# i2c.net
KiCad netlist of a schematic drawn in Altium Designer
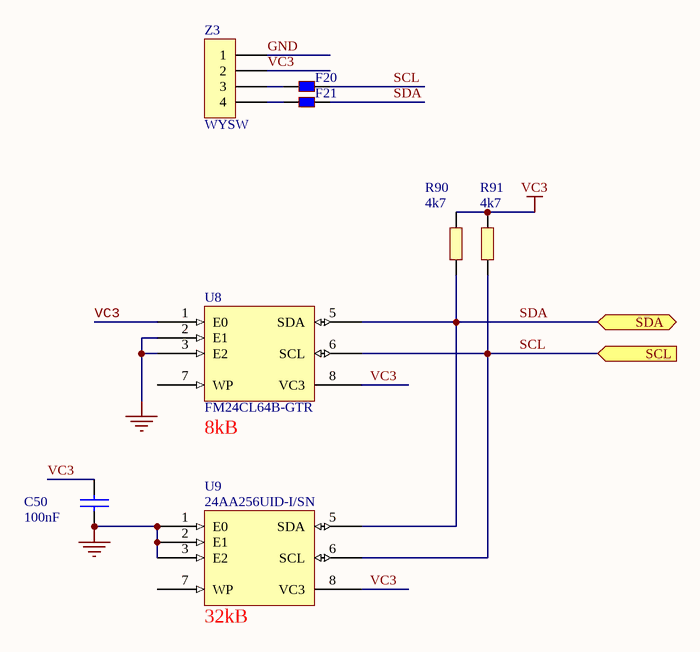
[diagram p0: i2c.SchDoc]

(export (version "E")
  (design (tool "Eeschema 10.0.6"))
  (components
    (comp (ref "C50")
      (value "100nF")
      (footprint "0603C")
      (description "Capacitor")
      (libsource (lib "*") (part "CAP"))
    )
    (comp (ref "F20")
      (value "BLM18BB141SN1D")
      (footprint "0603R")
      (description "Koralik ferrytowy")
      (libsource (lib "*") (part "1812"))
    )
    (comp (ref "F21")
      (value "BLM18BB141SN1D")
      (footprint "0603R")
      (description "Koralik ferrytowy")
      (libsource (lib "*") (part "1812"))
    )
    (comp (ref "R90") (value "4k7") (footprint "0603R") (libsource (lib "*") (part "RES3")))
    (comp (ref "R91") (value "4k7") (footprint "0603R") (libsource (lib "*") (part "RES3")))
    (comp (ref "U8") (value "FM24CL64B-GTR") (footprint "SO8") (libsource (lib "*") (part "AT24C02")))
    (comp (ref "U9") (value "24AA256UID-I/SN") (footprint "SO8") (libsource (lib "*") (part "AT24C02")))
    (comp (ref "Z3")
      (value "WYSW")
      (footprint "SSD1306_PR")
      (description "Connector")
      (libsource (lib "*") (part "CON4"))
    )
  )
  (nets
    (net (code "1") (name "/SCL") (class "Default")
      (node (ref "F20") (pin "2") (pintype "passive"))
      (node (ref "R91") (pin "2") (pintype "passive"))
      (node (ref "U8") (pin "6") (pinfunction "SCL_6") (pintype "bidirectional"))
      (node (ref "U9") (pin "6") (pinfunction "SCL_6") (pintype "bidirectional"))
    )
    (net (code "2") (name "/SDA") (class "Default")
      (node (ref "F21") (pin "2") (pintype "passive"))
      (node (ref "R90") (pin "2") (pintype "passive"))
      (node (ref "U8") (pin "5") (pinfunction "SDA_5") (pintype "bidirectional"))
      (node (ref "U9") (pin "5") (pinfunction "SDA_5") (pintype "bidirectional"))
    )
    (net (code "3") (name "GND") (class "Default")
      (node (ref "C50") (pin "2") (pinfunction "2_2") (pintype "passive"))
      (node (ref "U8") (pin "2") (pinfunction "E1_2") (pintype "input"))
      (node (ref "U8") (pin "3") (pinfunction "E2_3") (pintype "input"))
      (node (ref "U8") (pin "4") (pinfunction "GND_4") (pintype "power_in"))
      (node (ref "U9") (pin "1") (pinfunction "E0_1") (pintype "input"))
      (node (ref "U9") (pin "2") (pinfunction "E1_2") (pintype "input"))
      (node (ref "U9") (pin "3") (pinfunction "E2_3") (pintype "input"))
      (node (ref "U9") (pin "4") (pinfunction "GND_4") (pintype "power_in"))
      (node (ref "Z3") (pin "1") (pinfunction "1_1") (pintype "passive"))
    )
    (net (code "4") (name "Net-(F20-Pad1)") (class "Default")
      (node (ref "F20") (pin "1") (pintype "passive"))
      (node (ref "Z3") (pin "3") (pinfunction "3_3") (pintype "passive"))
    )
    (net (code "5") (name "Net-(F21-Pad1)") (class "Default")
      (node (ref "F21") (pin "1") (pintype "passive"))
      (node (ref "Z3") (pin "4") (pinfunction "4_4") (pintype "passive"))
    )
    (net (code "6") (name "VC3") (class "Default")
      (node (ref "C50") (pin "1") (pinfunction "1_1") (pintype "passive"))
      (node (ref "R90") (pin "1") (pintype "passive"))
      (node (ref "R91") (pin "1") (pintype "passive"))
      (node (ref "U8") (pin "1") (pinfunction "E0_1") (pintype "input"))
      (node (ref "U8") (pin "8") (pinfunction "VC3_8") (pintype "power_in"))
      (node (ref "U9") (pin "8") (pinfunction "VC3_8") (pintype "power_in"))
      (node (ref "Z3") (pin "2") (pinfunction "2_2") (pintype "passive"))
    )
    (net (code "7") (name "unconnected-(U8-WP-Pad7)") (class "Default")
      (node (ref "U8") (pin "7") (pinfunction "WP_7") (pintype "input"))
    )
    (net (code "8") (name "unconnected-(U9-WP-Pad7)") (class "Default")
      (node (ref "U9") (pin "7") (pinfunction "WP_7") (pintype "input"))
    )
  )
)
